# edp_millerv0_3.net
KiCad netlist of a schematic drawn in EAGLE
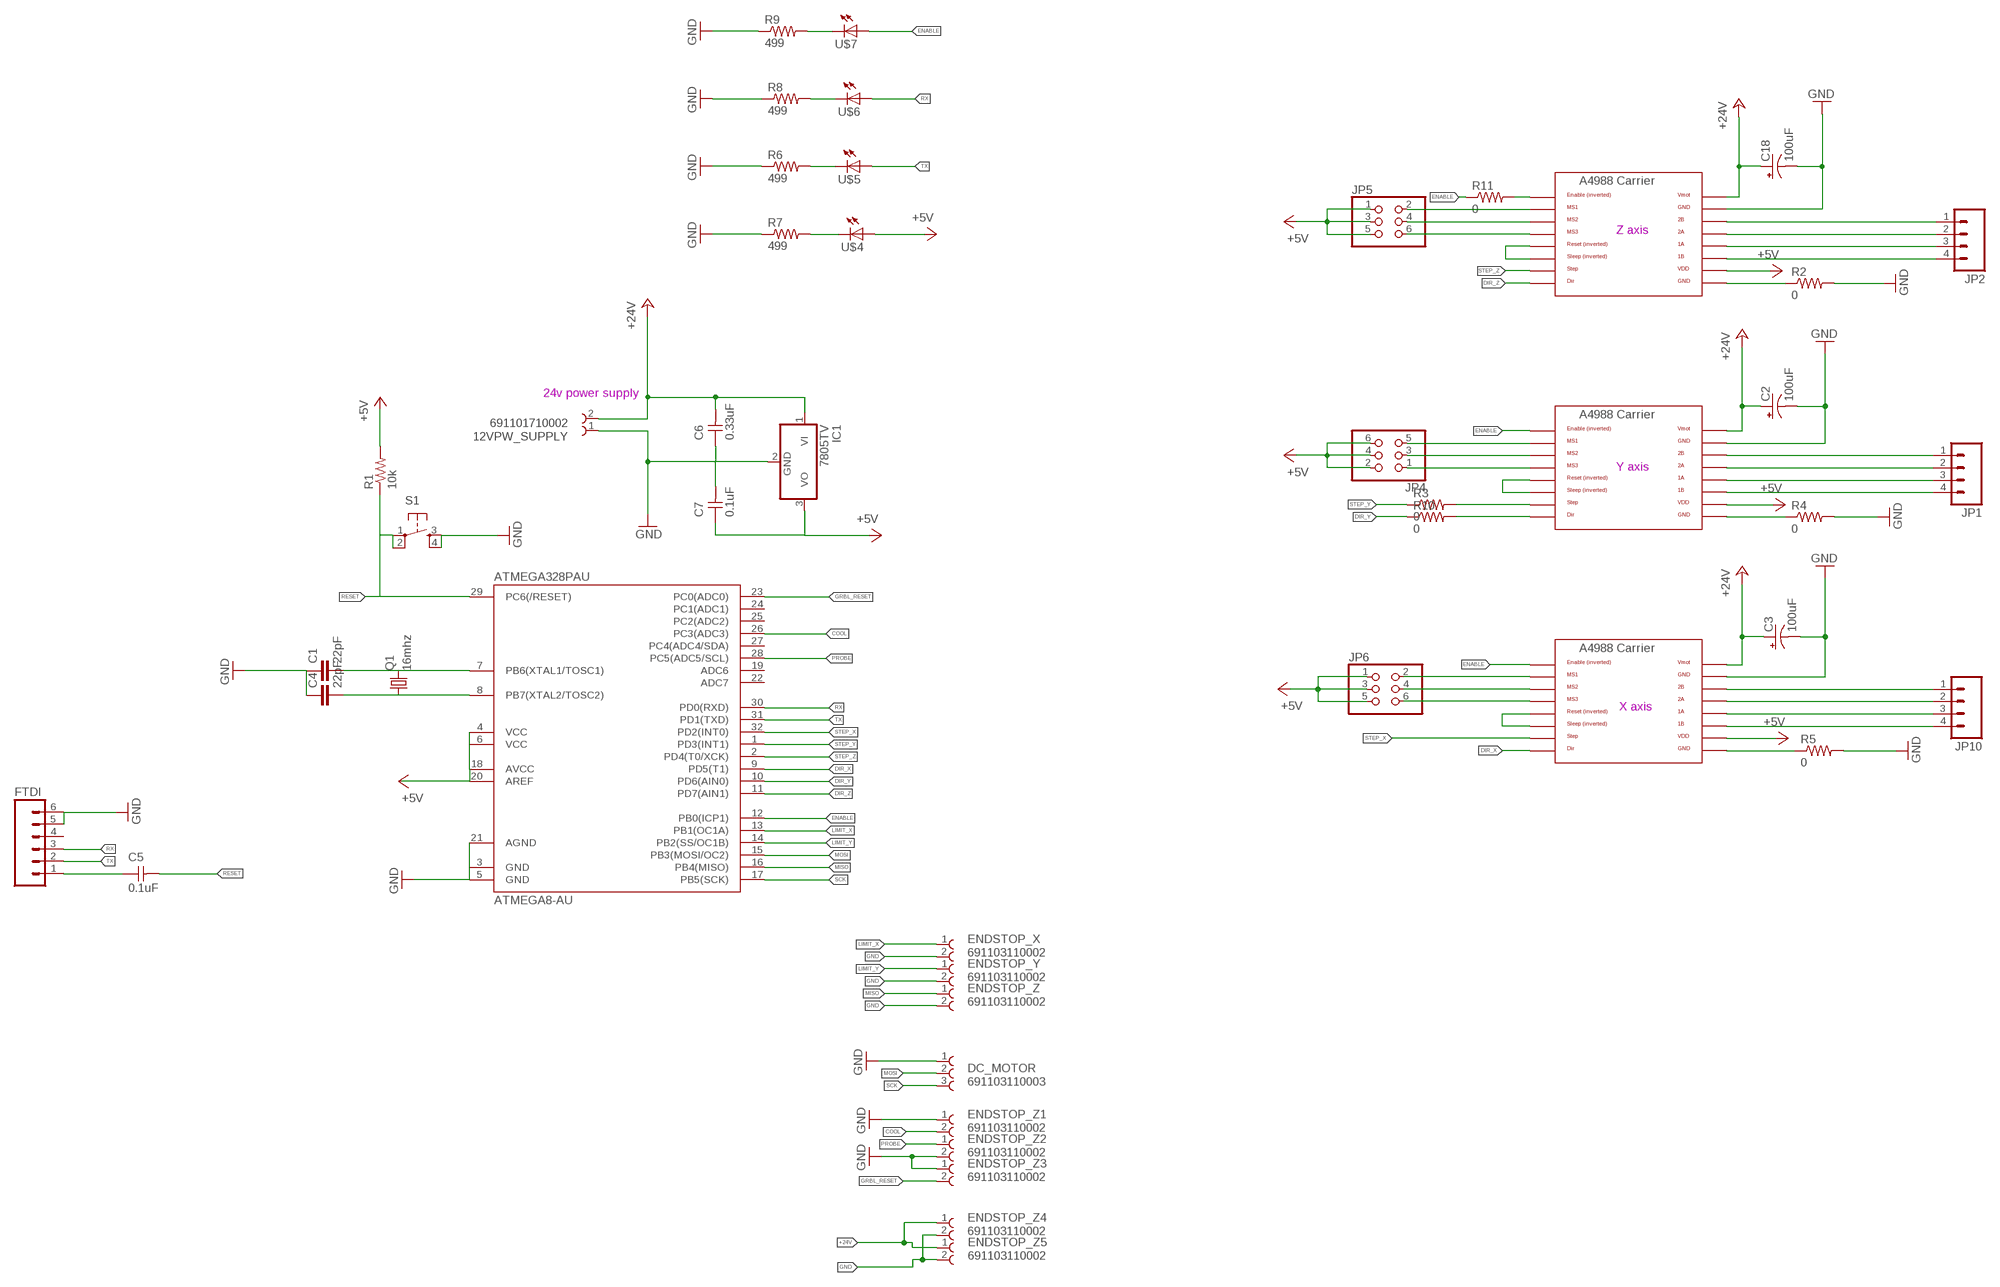
[diagram p0: schematic, sheet 1]

(export (version "E")
  (design (tool "Eeschema 10.0.6"))
  (components
    (comp (ref "12VPW_SUPPLY")
      (value "691101710002")
      (footprint "eagle-import:691101710002")
      (libsource (lib "eagle-import") (part "691101710002"))
    )
    (comp (ref "ATMEGA328PAU")
      (value "ATMEGA8-AU")
      (footprint "eagle-import:TQFP32-08")
      (libsource (lib "eagle-import") (part "ATMEGA8-AU"))
    )
    (comp (ref "C1")
      (value "22pF")
      (footprint "eagle-import:1206")
      (libsource (lib "eagle-import") (part "CAP1206"))
    )
    (comp (ref "C2")
      (value "100uF")
      (footprint "eagle-import:UD-10X10_NICHICON")
      (libsource (lib "eagle-import") (part "CPOL-USUD-10X10"))
    )
    (comp (ref "C3")
      (value "100uF")
      (footprint "eagle-import:UD-10X10_NICHICON")
      (libsource (lib "eagle-import") (part "CPOL-USUD-10X10"))
    )
    (comp (ref "C4")
      (value "22pF")
      (footprint "eagle-import:1206")
      (libsource (lib "eagle-import") (part "CAP1206"))
    )
    (comp (ref "C5")
      (value "0.1uF")
      (footprint "eagle-import:1206")
      (libsource (lib "eagle-import") (part "UNPOLARIZED_CAPACITOR1206"))
    )
    (comp (ref "C6")
      (value "0.33uF")
      (footprint "eagle-import:1206")
      (libsource (lib "eagle-import") (part "UNPOLARIZED_CAPACITOR1206"))
    )
    (comp (ref "C7")
      (value "0.1uF")
      (footprint "eagle-import:1206")
      (libsource (lib "eagle-import") (part "UNPOLARIZED_CAPACITOR1206"))
    )
    (comp (ref "C18")
      (value "100uF")
      (footprint "eagle-import:UD-10X10_NICHICON")
      (libsource (lib "eagle-import") (part "CPOL-USUD-10X10"))
    )
    (comp (ref "DC_MOTOR")
      (value "691103110003")
      (footprint "eagle-import:691103110003")
      (libsource (lib "eagle-import") (part "691103110003"))
    )
    (comp (ref "ENDSTOP_X")
      (value "691103110002")
      (footprint "eagle-import:691103110002")
      (libsource (lib "eagle-import") (part "691103110002"))
    )
    (comp (ref "ENDSTOP_Y")
      (value "691103110002")
      (footprint "eagle-import:691103110002")
      (libsource (lib "eagle-import") (part "691103110002"))
    )
    (comp (ref "ENDSTOP_Z")
      (value "691103110002")
      (footprint "eagle-import:691103110002")
      (libsource (lib "eagle-import") (part "691103110002"))
    )
    (comp (ref "ENDSTOP_Z1")
      (value "691103110002")
      (footprint "eagle-import:691103110002")
      (libsource (lib "eagle-import") (part "691103110002"))
    )
    (comp (ref "ENDSTOP_Z2")
      (value "691103110002")
      (footprint "eagle-import:691103110002")
      (libsource (lib "eagle-import") (part "691103110002"))
    )
    (comp (ref "ENDSTOP_Z3")
      (value "691103110002")
      (footprint "eagle-import:691103110002")
      (libsource (lib "eagle-import") (part "691103110002"))
    )
    (comp (ref "ENDSTOP_Z4")
      (value "691103110002")
      (footprint "eagle-import:691103110002")
      (libsource (lib "eagle-import") (part "691103110002"))
    )
    (comp (ref "ENDSTOP_Z5")
      (value "691103110002")
      (footprint "eagle-import:691103110002")
      (libsource (lib "eagle-import") (part "691103110002"))
    )
    (comp (ref "FTDI")
      (value "M06SMD")
      (footprint "eagle-import:1X06-SMD")
      (libsource (lib "eagle-import") (part "M06SMD"))
    )
    (comp (ref "IC1")
      (value "7805TV")
      (footprint "eagle-import:TO220V")
      (libsource (lib "eagle-import") (part "78TV05"))
    )
    (comp (ref "JP1")
      (value "M04LONGPADS")
      (footprint "eagle-import:1X04_LONGPADS")
      (libsource (lib "eagle-import") (part "M04LONGPADS"))
    )
    (comp (ref "JP2")
      (value "M04LONGPADS")
      (footprint "eagle-import:1X04_LONGPADS")
      (libsource (lib "eagle-import") (part "M04LONGPADS"))
    )
    (comp (ref "JP4")
      (value "PINHD-2X3-SMD")
      (footprint "eagle-import:2X03SMD")
      (libsource (lib "eagle-import") (part "PINHD-2X3-SMD"))
    )
    (comp (ref "JP5")
      (value "PINHD-2X3-SMD")
      (footprint "eagle-import:2X03SMD")
      (libsource (lib "eagle-import") (part "PINHD-2X3-SMD"))
    )
    (comp (ref "JP6")
      (value "PINHD-2X3-SMD")
      (footprint "eagle-import:2X03SMD")
      (libsource (lib "eagle-import") (part "PINHD-2X3-SMD"))
    )
    (comp (ref "JP10")
      (value "M04LONGPADS")
      (footprint "eagle-import:1X04_LONGPADS")
      (libsource (lib "eagle-import") (part "M04LONGPADS"))
    )
    (comp (ref "Q1")
      (value "16mhz")
      (footprint "eagle-import:CSM-7X-DU")
      (libsource (lib "eagle-import") (part "CSM-7X-DU"))
    )
    (comp (ref "R1")
      (value "10k")
      (footprint "eagle-import:1206")
      (libsource (lib "eagle-import") (part "01_SparkFun_RESISTOR1206"))
    )
    (comp (ref "R2")
      (value "0")
      (footprint "eagle-import:1206")
      (libsource (lib "eagle-import") (part "01_SparkFun_RESISTOR1206"))
    )
    (comp (ref "R3")
      (value "0")
      (footprint "eagle-import:1206")
      (libsource (lib "eagle-import") (part "01_SparkFun_RESISTOR1206"))
    )
    (comp (ref "R4")
      (value "0")
      (footprint "eagle-import:1206")
      (libsource (lib "eagle-import") (part "01_SparkFun_RESISTOR1206"))
    )
    (comp (ref "R5")
      (value "0")
      (footprint "eagle-import:1206")
      (libsource (lib "eagle-import") (part "01_SparkFun_RESISTOR1206"))
    )
    (comp (ref "R6")
      (value "499")
      (footprint "eagle-import:1206")
      (libsource (lib "eagle-import") (part "RESISTOR1206"))
    )
    (comp (ref "R7")
      (value "499")
      (footprint "eagle-import:1206")
      (libsource (lib "eagle-import") (part "RESISTOR1206"))
    )
    (comp (ref "R8")
      (value "499")
      (footprint "eagle-import:1206")
      (libsource (lib "eagle-import") (part "RESISTOR1206"))
    )
    (comp (ref "R9")
      (value "499")
      (footprint "eagle-import:1206")
      (libsource (lib "eagle-import") (part "RESISTOR1206"))
    )
    (comp (ref "R10")
      (value "0")
      (footprint "eagle-import:1206")
      (libsource (lib "eagle-import") (part "01_SparkFun_RESISTOR1206"))
    )
    (comp (ref "R11")
      (value "0")
      (footprint "eagle-import:1206")
      (libsource (lib "eagle-import") (part "01_SparkFun_RESISTOR1206"))
    )
    (comp (ref "S1")
      (value "6MM_SWITCH6MM_SWITCH")
      (footprint "eagle-import:6MM_SWITCH")
      (libsource (lib "eagle-import") (part "6MM_SWITCH6MM_SWITCH"))
    )
    (comp (ref "U$1")
      (value "POLOLU_A4983CARRIER")
      (footprint "eagle-import:A4988BREAKOUT")
      (libsource (lib "eagle-import") (part "POLOLU_A4983CARRIER"))
    )
    (comp (ref "U$2")
      (value "POLOLU_A4983CARRIER")
      (footprint "eagle-import:A4988BREAKOUT")
      (libsource (lib "eagle-import") (part "POLOLU_A4983CARRIER"))
    )
    (comp (ref "U$3")
      (value "POLOLU_A4983CARRIER")
      (footprint "eagle-import:A4988BREAKOUT")
      (libsource (lib "eagle-import") (part "POLOLU_A4983CARRIER"))
    )
    (comp (ref "U$4")
      (value "LED1206")
      (footprint "eagle-import:1206")
      (libsource (lib "eagle-import") (part "LED1206"))
    )
    (comp (ref "U$5")
      (value "LED1206")
      (footprint "eagle-import:1206")
      (libsource (lib "eagle-import") (part "LED1206"))
    )
    (comp (ref "U$6")
      (value "LED1206")
      (footprint "eagle-import:1206")
      (libsource (lib "eagle-import") (part "LED1206"))
    )
    (comp (ref "U$7")
      (value "LED1206")
      (footprint "eagle-import:1206")
      (libsource (lib "eagle-import") (part "LED1206"))
    )
  )
  (nets
    (net (code "1") (name "+5V") (class "Default")
      (node (ref "ATMEGA328PAU") (pin "18") (pinfunction "AVCC_18") (pintype "passive"))
      (node (ref "ATMEGA328PAU") (pin "20") (pinfunction "AREF_20") (pintype "passive"))
      (node (ref "ATMEGA328PAU") (pin "4") (pinfunction "VCC_4") (pintype "power_in"))
      (node (ref "ATMEGA328PAU") (pin "6") (pinfunction "VCC_6") (pintype "power_in"))
      (node (ref "C7") (pin "1") (pinfunction "1_1") (pintype "passive"))
      (node (ref "IC1") (pin "3") (pinfunction "VO_3") (pintype "passive"))
      (node (ref "JP4") (pin "2") (pinfunction "2_2") (pintype "passive"))
      (node (ref "JP4") (pin "4") (pinfunction "4_4") (pintype "passive"))
      (node (ref "JP4") (pin "6") (pinfunction "6_6") (pintype "passive"))
      (node (ref "JP5") (pin "1") (pinfunction "1_1") (pintype "passive"))
      (node (ref "JP5") (pin "3") (pinfunction "3_3") (pintype "passive"))
      (node (ref "JP5") (pin "5") (pinfunction "5_5") (pintype "passive"))
      (node (ref "JP6") (pin "1") (pinfunction "1_1") (pintype "passive"))
      (node (ref "JP6") (pin "3") (pinfunction "3_3") (pintype "passive"))
      (node (ref "JP6") (pin "5") (pinfunction "5_5") (pintype "passive"))
      (node (ref "R1") (pin "2") (pinfunction "2_2") (pintype "passive"))
      (node (ref "U$1") (pin "VDD") (pinfunction "VDD_VDD") (pintype "power_in"))
      (node (ref "U$2") (pin "VDD") (pinfunction "VDD_VDD") (pintype "power_in"))
      (node (ref "U$3") (pin "VDD") (pinfunction "VDD_VDD") (pintype "power_in"))
      (node (ref "U$4") (pin "1") (pinfunction "A_1") (pintype "passive"))
    )
    (net (code "2") (name "+24V") (class "Default")
      (node (ref "12VPW_SUPPLY") (pin "2") (pinfunction "2_2") (pintype "passive"))
      (node (ref "C18") (pin "+") (pinfunction "+_+") (pintype "passive"))
      (node (ref "C2") (pin "+") (pinfunction "+_+") (pintype "passive"))
      (node (ref "C3") (pin "+") (pinfunction "+_+") (pintype "passive"))
      (node (ref "C6") (pin "2") (pinfunction "2_2") (pintype "passive"))
      (node (ref "ENDSTOP_Z4") (pin "1") (pinfunction "1_1") (pintype "passive"))
      (node (ref "ENDSTOP_Z5") (pin "1") (pinfunction "1_1") (pintype "passive"))
      (node (ref "IC1") (pin "1") (pinfunction "VI_1") (pintype "input"))
      (node (ref "U$1") (pin "VMOT") (pinfunction "VMOT_VMOT") (pintype "power_in"))
      (node (ref "U$2") (pin "VMOT") (pinfunction "VMOT_VMOT") (pintype "power_in"))
      (node (ref "U$3") (pin "VMOT") (pinfunction "VMOT_VMOT") (pintype "power_in"))
    )
    (net (code "3") (name "COOL") (class "Default")
      (node (ref "ATMEGA328PAU") (pin "26") (pinfunction "PC3(ADC3)_26") (pintype "bidirectional"))
      (node (ref "ENDSTOP_Z1") (pin "2") (pinfunction "2_2") (pintype "passive"))
    )
    (net (code "4") (name "DIR_X") (class "Default")
      (node (ref "ATMEGA328PAU") (pin "9") (pinfunction "PD5(T1)_9") (pintype "bidirectional"))
      (node (ref "U$3") (pin "DIR") (pinfunction "DIR_DIR") (pintype "input"))
    )
    (net (code "5") (name "DIR_Y") (class "Default")
      (node (ref "ATMEGA328PAU") (pin "10") (pinfunction "PD6(AIN0)_10") (pintype "bidirectional"))
      (node (ref "R10") (pin "1") (pinfunction "1_1") (pintype "passive"))
    )
    (net (code "6") (name "DIR_Z") (class "Default")
      (node (ref "ATMEGA328PAU") (pin "11") (pinfunction "PD7(AIN1)_11") (pintype "bidirectional"))
      (node (ref "U$2") (pin "DIR") (pinfunction "DIR_DIR") (pintype "input"))
    )
    (net (code "7") (name "ENABLE") (class "Default")
      (node (ref "ATMEGA328PAU") (pin "12") (pinfunction "PB0(ICP1)_12") (pintype "bidirectional"))
      (node (ref "R11") (pin "1") (pinfunction "1_1") (pintype "passive"))
      (node (ref "R11") (pin "2") (pinfunction "2_2") (pintype "passive"))
      (node (ref "U$1") (pin "EN") (pinfunction "EN_EN") (pintype "input"))
      (node (ref "U$2") (pin "EN") (pinfunction "EN_EN") (pintype "input"))
      (node (ref "U$3") (pin "EN") (pinfunction "EN_EN") (pintype "input"))
      (node (ref "U$7") (pin "1") (pinfunction "A_1") (pintype "passive"))
    )
    (net (code "8") (name "GND") (class "Default")
      (node (ref "12VPW_SUPPLY") (pin "1") (pinfunction "1_1") (pintype "passive"))
      (node (ref "ATMEGA328PAU") (pin "21") (pinfunction "AGND_21") (pintype "power_in"))
      (node (ref "ATMEGA328PAU") (pin "3") (pinfunction "GND_3") (pintype "power_in"))
      (node (ref "ATMEGA328PAU") (pin "5") (pinfunction "GND_5") (pintype "power_in"))
      (node (ref "C1") (pin "1") (pinfunction "1_1") (pintype "passive"))
      (node (ref "C18") (pin "-") (pinfunction "-_-") (pintype "passive"))
      (node (ref "C2") (pin "-") (pinfunction "-_-") (pintype "passive"))
      (node (ref "C3") (pin "-") (pinfunction "-_-") (pintype "passive"))
      (node (ref "C4") (pin "1") (pinfunction "1_1") (pintype "passive"))
      (node (ref "C6") (pin "1") (pinfunction "1_1") (pintype "passive"))
      (node (ref "C7") (pin "2") (pinfunction "2_2") (pintype "passive"))
      (node (ref "DC_MOTOR") (pin "1") (pinfunction "1_1") (pintype "passive"))
      (node (ref "ENDSTOP_X") (pin "2") (pinfunction "2_2") (pintype "passive"))
      (node (ref "ENDSTOP_Y") (pin "2") (pinfunction "2_2") (pintype "passive"))
      (node (ref "ENDSTOP_Z") (pin "2") (pinfunction "2_2") (pintype "passive"))
      (node (ref "ENDSTOP_Z1") (pin "1") (pinfunction "1_1") (pintype "passive"))
      (node (ref "ENDSTOP_Z2") (pin "2") (pinfunction "2_2") (pintype "passive"))
      (node (ref "ENDSTOP_Z3") (pin "1") (pinfunction "1_1") (pintype "passive"))
      (node (ref "ENDSTOP_Z4") (pin "2") (pinfunction "2_2") (pintype "passive"))
      (node (ref "ENDSTOP_Z5") (pin "2") (pinfunction "2_2") (pintype "passive"))
      (node (ref "FTDI") (pin "5") (pinfunction "5_5") (pintype "passive"))
      (node (ref "FTDI") (pin "6") (pinfunction "6_6") (pintype "passive"))
      (node (ref "IC1") (pin "2") (pinfunction "GND_2") (pintype "passive"))
      (node (ref "R2") (pin "1") (pinfunction "1_1") (pintype "passive"))
      (node (ref "R2") (pin "2") (pinfunction "2_2") (pintype "passive"))
      (node (ref "R4") (pin "1") (pinfunction "1_1") (pintype "passive"))
      (node (ref "R4") (pin "2") (pinfunction "2_2") (pintype "passive"))
      (node (ref "R5") (pin "1") (pinfunction "1_1") (pintype "passive"))
      (node (ref "R5") (pin "2") (pinfunction "2_2") (pintype "passive"))
      (node (ref "R6") (pin "1") (pinfunction "1_1") (pintype "passive"))
      (node (ref "R7") (pin "1") (pinfunction "1_1") (pintype "passive"))
      (node (ref "R8") (pin "1") (pinfunction "1_1") (pintype "passive"))
      (node (ref "R9") (pin "1") (pinfunction "1_1") (pintype "passive"))
      (node (ref "S1") (pin "3") (pinfunction "S_3") (pintype "passive"))
      (node (ref "S1") (pin "4") (pinfunction "S1_4") (pintype "passive"))
      (node (ref "U$1") (pin "GND") (pinfunction "GND_GND") (pintype "power_in"))
      (node (ref "U$1") (pin "GND@0") (pinfunction "GND_GND@0") (pintype "power_in"))
      (node (ref "U$2") (pin "GND") (pinfunction "GND_GND") (pintype "power_in"))
      (node (ref "U$2") (pin "GND@0") (pinfunction "GND_GND@0") (pintype "power_in"))
      (node (ref "U$3") (pin "GND") (pinfunction "GND_GND") (pintype "power_in"))
      (node (ref "U$3") (pin "GND@0") (pinfunction "GND_GND@0") (pintype "power_in"))
    )
    (net (code "9") (name "GRBL_RESET") (class "Default")
      (node (ref "ATMEGA328PAU") (pin "23") (pinfunction "PC0(ADC0)_23") (pintype "bidirectional"))
      (node (ref "ENDSTOP_Z3") (pin "2") (pinfunction "2_2") (pintype "passive"))
    )
    (net (code "10") (name "LIMIT_X") (class "Default")
      (node (ref "ATMEGA328PAU") (pin "13") (pinfunction "PB1(OC1A)_13") (pintype "bidirectional"))
      (node (ref "ENDSTOP_X") (pin "1") (pinfunction "1_1") (pintype "passive"))
    )
    (net (code "11") (name "LIMIT_Y") (class "Default")
      (node (ref "ATMEGA328PAU") (pin "14") (pinfunction "PB2(SS/OC1B)_14") (pintype "bidirectional"))
      (node (ref "ENDSTOP_Y") (pin "1") (pinfunction "1_1") (pintype "passive"))
    )
    (net (code "12") (name "MISO") (class "Default")
      (node (ref "ATMEGA328PAU") (pin "16") (pinfunction "PB4(MISO)_16") (pintype "bidirectional"))
      (node (ref "ENDSTOP_Z") (pin "1") (pinfunction "1_1") (pintype "passive"))
    )
    (net (code "13") (name "MOSI") (class "Default")
      (node (ref "ATMEGA328PAU") (pin "15") (pinfunction "PB3(MOSI/OC2)_15") (pintype "bidirectional"))
      (node (ref "DC_MOTOR") (pin "2") (pinfunction "2_2") (pintype "passive"))
    )
    (net (code "14") (name "Net-(ATMEGA328PAU-PB6(XTAL1{slash}TOSC1))") (class "Default")
      (node (ref "ATMEGA328PAU") (pin "7") (pinfunction "PB6(XTAL1/TOSC1)_7") (pintype "bidirectional"))
      (node (ref "C1") (pin "2") (pinfunction "2_2") (pintype "passive"))
      (node (ref "Q1") (pin "2") (pinfunction "2_2") (pintype "passive"))
    )
    (net (code "15") (name "Net-(ATMEGA328PAU-PB7(XTAL2{slash}TOSC2))") (class "Default")
      (node (ref "ATMEGA328PAU") (pin "8") (pinfunction "PB7(XTAL2/TOSC2)_8") (pintype "bidirectional"))
      (node (ref "C4") (pin "2") (pinfunction "2_2") (pintype "passive"))
      (node (ref "Q1") (pin "1") (pinfunction "1_1") (pintype "passive"))
    )
    (net (code "16") (name "Net-(C5-Pad1)") (class "Default")
      (node (ref "C5") (pin "1") (pinfunction "1_1") (pintype "passive"))
      (node (ref "FTDI") (pin "1") (pinfunction "1_1") (pintype "passive"))
    )
    (net (code "17") (name "Net-(JP1-Pad1)") (class "Default")
      (node (ref "JP1") (pin "1") (pinfunction "1_1") (pintype "passive"))
      (node (ref "U$1") (pin "2B") (pinfunction "2B_2B") (pintype "output"))
    )
    (net (code "18") (name "Net-(JP1-Pad2)") (class "Default")
      (node (ref "JP1") (pin "2") (pinfunction "2_2") (pintype "passive"))
      (node (ref "U$1") (pin "2A") (pinfunction "2A_2A") (pintype "output"))
    )
    (net (code "19") (name "Net-(JP1-Pad3)") (class "Default")
      (node (ref "JP1") (pin "3") (pinfunction "3_3") (pintype "passive"))
      (node (ref "U$1") (pin "1A") (pinfunction "1A_1A") (pintype "output"))
    )
    (net (code "20") (name "Net-(JP1-Pad4)") (class "Default")
      (node (ref "JP1") (pin "4") (pinfunction "4_4") (pintype "passive"))
      (node (ref "U$1") (pin "1B") (pinfunction "1B_1B") (pintype "output"))
    )
    (net (code "21") (name "Net-(JP2-Pad1)") (class "Default")
      (node (ref "JP2") (pin "1") (pinfunction "1_1") (pintype "passive"))
      (node (ref "U$2") (pin "2B") (pinfunction "2B_2B") (pintype "output"))
    )
    (net (code "22") (name "Net-(JP2-Pad2)") (class "Default")
      (node (ref "JP2") (pin "2") (pinfunction "2_2") (pintype "passive"))
      (node (ref "U$2") (pin "2A") (pinfunction "2A_2A") (pintype "output"))
    )
    (net (code "23") (name "Net-(JP2-Pad3)") (class "Default")
      (node (ref "JP2") (pin "3") (pinfunction "3_3") (pintype "passive"))
      (node (ref "U$2") (pin "1A") (pinfunction "1A_1A") (pintype "output"))
    )
    (net (code "24") (name "Net-(JP2-Pad4)") (class "Default")
      (node (ref "JP2") (pin "4") (pinfunction "4_4") (pintype "passive"))
      (node (ref "U$2") (pin "1B") (pinfunction "1B_1B") (pintype "output"))
    )
    (net (code "25") (name "Net-(JP4-Pad1)") (class "Default")
      (node (ref "JP4") (pin "1") (pinfunction "1_1") (pintype "passive"))
      (node (ref "U$1") (pin "MS3") (pinfunction "MS3_MS3") (pintype "input"))
    )
    (net (code "26") (name "Net-(JP4-Pad3)") (class "Default")
      (node (ref "JP4") (pin "3") (pinfunction "3_3") (pintype "passive"))
      (node (ref "U$1") (pin "MS2") (pinfunction "MS2_MS2") (pintype "input"))
    )
    (net (code "27") (name "Net-(JP4-Pad5)") (class "Default")
      (node (ref "JP4") (pin "5") (pinfunction "5_5") (pintype "passive"))
      (node (ref "U$1") (pin "MS1") (pinfunction "MS1_MS1") (pintype "input"))
    )
    (net (code "28") (name "Net-(JP5-Pad2)") (class "Default")
      (node (ref "JP5") (pin "2") (pinfunction "2_2") (pintype "passive"))
      (node (ref "U$2") (pin "MS1") (pinfunction "MS1_MS1") (pintype "input"))
    )
    (net (code "29") (name "Net-(JP5-Pad4)") (class "Default")
      (node (ref "JP5") (pin "4") (pinfunction "4_4") (pintype "passive"))
      (node (ref "U$2") (pin "MS2") (pinfunction "MS2_MS2") (pintype "input"))
    )
    (net (code "30") (name "Net-(JP5-Pad6)") (class "Default")
      (node (ref "JP5") (pin "6") (pinfunction "6_6") (pintype "passive"))
      (node (ref "U$2") (pin "MS3") (pinfunction "MS3_MS3") (pintype "input"))
    )
    (net (code "31") (name "Net-(JP6-Pad2)") (class "Default")
      (node (ref "JP6") (pin "2") (pinfunction "2_2") (pintype "passive"))
      (node (ref "U$3") (pin "MS1") (pinfunction "MS1_MS1") (pintype "input"))
    )
    (net (code "32") (name "Net-(JP6-Pad4)") (class "Default")
      (node (ref "JP6") (pin "4") (pinfunction "4_4") (pintype "passive"))
      (node (ref "U$3") (pin "MS2") (pinfunction "MS2_MS2") (pintype "input"))
    )
    (net (code "33") (name "Net-(JP6-Pad6)") (class "Default")
      (node (ref "JP6") (pin "6") (pinfunction "6_6") (pintype "passive"))
      (node (ref "U$3") (pin "MS3") (pinfunction "MS3_MS3") (pintype "input"))
    )
    (net (code "34") (name "Net-(JP10-Pad1)") (class "Default")
      (node (ref "JP10") (pin "1") (pinfunction "1_1") (pintype "passive"))
      (node (ref "U$3") (pin "2B") (pinfunction "2B_2B") (pintype "output"))
    )
    (net (code "35") (name "Net-(JP10-Pad2)") (class "Default")
      (node (ref "JP10") (pin "2") (pinfunction "2_2") (pintype "passive"))
      (node (ref "U$3") (pin "2A") (pinfunction "2A_2A") (pintype "output"))
    )
    (net (code "36") (name "Net-(JP10-Pad3)") (class "Default")
      (node (ref "JP10") (pin "3") (pinfunction "3_3") (pintype "passive"))
      (node (ref "U$3") (pin "1A") (pinfunction "1A_1A") (pintype "output"))
    )
    (net (code "37") (name "Net-(JP10-Pad4)") (class "Default")
      (node (ref "JP10") (pin "4") (pinfunction "4_4") (pintype "passive"))
      (node (ref "U$3") (pin "1B") (pinfunction "1B_1B") (pintype "output"))
    )
    (net (code "38") (name "Net-(R3-Pad2)") (class "Default")
      (node (ref "R3") (pin "2") (pinfunction "2_2") (pintype "passive"))
      (node (ref "U$1") (pin "STEP") (pinfunction "STEP_STEP") (pintype "input"))
    )
    (net (code "39") (name "Net-(R10-Pad2)") (class "Default")
      (node (ref "R10") (pin "2") (pinfunction "2_2") (pintype "passive"))
      (node (ref "U$1") (pin "DIR") (pinfunction "DIR_DIR") (pintype "input"))
    )
    (net (code "40") (name "Net-(U$1-SLEEP)") (class "Default")
      (node (ref "U$1") (pin "RST") (pinfunction "RST_RST") (pintype "input"))
      (node (ref "U$1") (pin "SLP") (pinfunction "SLEEP_SLP") (pintype "input"))
    )
    (net (code "41") (name "Net-(U$2-SLEEP)") (class "Default")
      (node (ref "U$2") (pin "RST") (pinfunction "RST_RST") (pintype "input"))
      (node (ref "U$2") (pin "SLP") (pinfunction "SLEEP_SLP") (pintype "input"))
    )
    (net (code "42") (name "Net-(U$3-SLEEP)") (class "Default")
      (node (ref "U$3") (pin "RST") (pinfunction "RST_RST") (pintype "input"))
      (node (ref "U$3") (pin "SLP") (pinfunction "SLEEP_SLP") (pintype "input"))
    )
    (net (code "43") (name "Net-(U$4-C)") (class "Default")
      (node (ref "R7") (pin "2") (pinfunction "2_2") (pintype "passive"))
      (node (ref "U$4") (pin "2") (pinfunction "C_2") (pintype "passive"))
    )
    (net (code "44") (name "Net-(U$5-C)") (class "Default")
      (node (ref "R6") (pin "2") (pinfunction "2_2") (pintype "passive"))
      (node (ref "U$5") (pin "2") (pinfunction "C_2") (pintype "passive"))
    )
    (net (code "45") (name "Net-(U$6-C)") (class "Default")
      (node (ref "R8") (pin "2") (pinfunction "2_2") (pintype "passive"))
      (node (ref "U$6") (pin "2") (pinfunction "C_2") (pintype "passive"))
    )
    (net (code "46") (name "Net-(U$7-C)") (class "Default")
      (node (ref "R9") (pin "2") (pinfunction "2_2") (pintype "passive"))
      (node (ref "U$7") (pin "2") (pinfunction "C_2") (pintype "passive"))
    )
    (net (code "47") (name "PROBE") (class "Default")
      (node (ref "ATMEGA328PAU") (pin "28") (pinfunction "PC5(ADC5/SCL)_28") (pintype "bidirectional"))
      (node (ref "ENDSTOP_Z2") (pin "1") (pinfunction "1_1") (pintype "passive"))
    )
    (net (code "48") (name "RESET") (class "Default")
      (node (ref "ATMEGA328PAU") (pin "29") (pinfunction "PC6(/RESET)_29") (pintype "bidirectional"))
      (node (ref "C5") (pin "2") (pinfunction "2_2") (pintype "passive"))
      (node (ref "R1") (pin "1") (pinfunction "1_1") (pintype "passive"))
      (node (ref "S1") (pin "1") (pinfunction "P_1") (pintype "passive"))
      (node (ref "S1") (pin "2") (pinfunction "P1_2") (pintype "passive"))
    )
    (net (code "49") (name "RX") (class "Default")
      (node (ref "ATMEGA328PAU") (pin "30") (pinfunction "PD0(RXD)_30") (pintype "bidirectional"))
      (node (ref "FTDI") (pin "3") (pinfunction "3_3") (pintype "passive"))
      (node (ref "U$6") (pin "1") (pinfunction "A_1") (pintype "passive"))
    )
    (net (code "50") (name "SCK") (class "Default")
      (node (ref "ATMEGA328PAU") (pin "17") (pinfunction "PB5(SCK)_17") (pintype "bidirectional"))
      (node (ref "DC_MOTOR") (pin "3") (pinfunction "3_3") (pintype "passive"))
    )
    (net (code "51") (name "STEP_X") (class "Default")
      (node (ref "ATMEGA328PAU") (pin "32") (pinfunction "PD2(INT0)_32") (pintype "bidirectional"))
      (node (ref "U$3") (pin "STEP") (pinfunction "STEP_STEP") (pintype "input"))
    )
    (net (code "52") (name "STEP_Y") (class "Default")
      (node (ref "ATMEGA328PAU") (pin "1") (pinfunction "PD3(INT1)_1") (pintype "bidirectional"))
      (node (ref "R3") (pin "1") (pinfunction "1_1") (pintype "passive"))
    )
    (net (code "53") (name "STEP_Z") (class "Default")
      (node (ref "ATMEGA328PAU") (pin "2") (pinfunction "PD4(T0/XCK)_2") (pintype "bidirectional"))
      (node (ref "U$2") (pin "STEP") (pinfunction "STEP_STEP") (pintype "input"))
    )
    (net (code "54") (name "TX") (class "Default")
      (node (ref "ATMEGA328PAU") (pin "31") (pinfunction "PD1(TXD)_31") (pintype "bidirectional"))
      (node (ref "FTDI") (pin "2") (pinfunction "2_2") (pintype "passive"))
      (node (ref "U$5") (pin "1") (pinfunction "A_1") (pintype "passive"))
    )
    (net (code "55") (name "unconnected-(ATMEGA328PAU-ADC6-Pad19)") (class "Default")
      (node (ref "ATMEGA328PAU") (pin "19") (pinfunction "ADC6_19") (pintype "passive"))
    )
    (net (code "56") (name "unconnected-(ATMEGA328PAU-ADC7-Pad22)") (class "Default")
      (node (ref "ATMEGA328PAU") (pin "22") (pinfunction "ADC7_22") (pintype "passive"))
    )
    (net (code "57") (name "unconnected-(ATMEGA328PAU-PC1(ADC1)-Pad24)") (class "Default")
      (node (ref "ATMEGA328PAU") (pin "24") (pinfunction "PC1(ADC1)_24") (pintype "bidirectional"))
    )
    (net (code "58") (name "unconnected-(ATMEGA328PAU-PC2(ADC2)-Pad25)") (class "Default")
      (node (ref "ATMEGA328PAU") (pin "25") (pinfunction "PC2(ADC2)_25") (pintype "bidirectional"))
    )
    (net (code "59") (name "unconnected-(ATMEGA328PAU-PC4(ADC4{slash}SDA)-Pad27)") (class "Default")
      (node (ref "ATMEGA328PAU") (pin "27") (pinfunction "PC4(ADC4/SDA)_27") (pintype "bidirectional"))
    )
    (net (code "60") (name "unconnected-(FTDI-Pad4)") (class "Default")
      (node (ref "FTDI") (pin "4") (pinfunction "4_4") (pintype "passive"))
    )
  )
)
